# ETH10M100M_RMII_LAN8720.net
KiCad netlist of a schematic drawn in Altium Designer
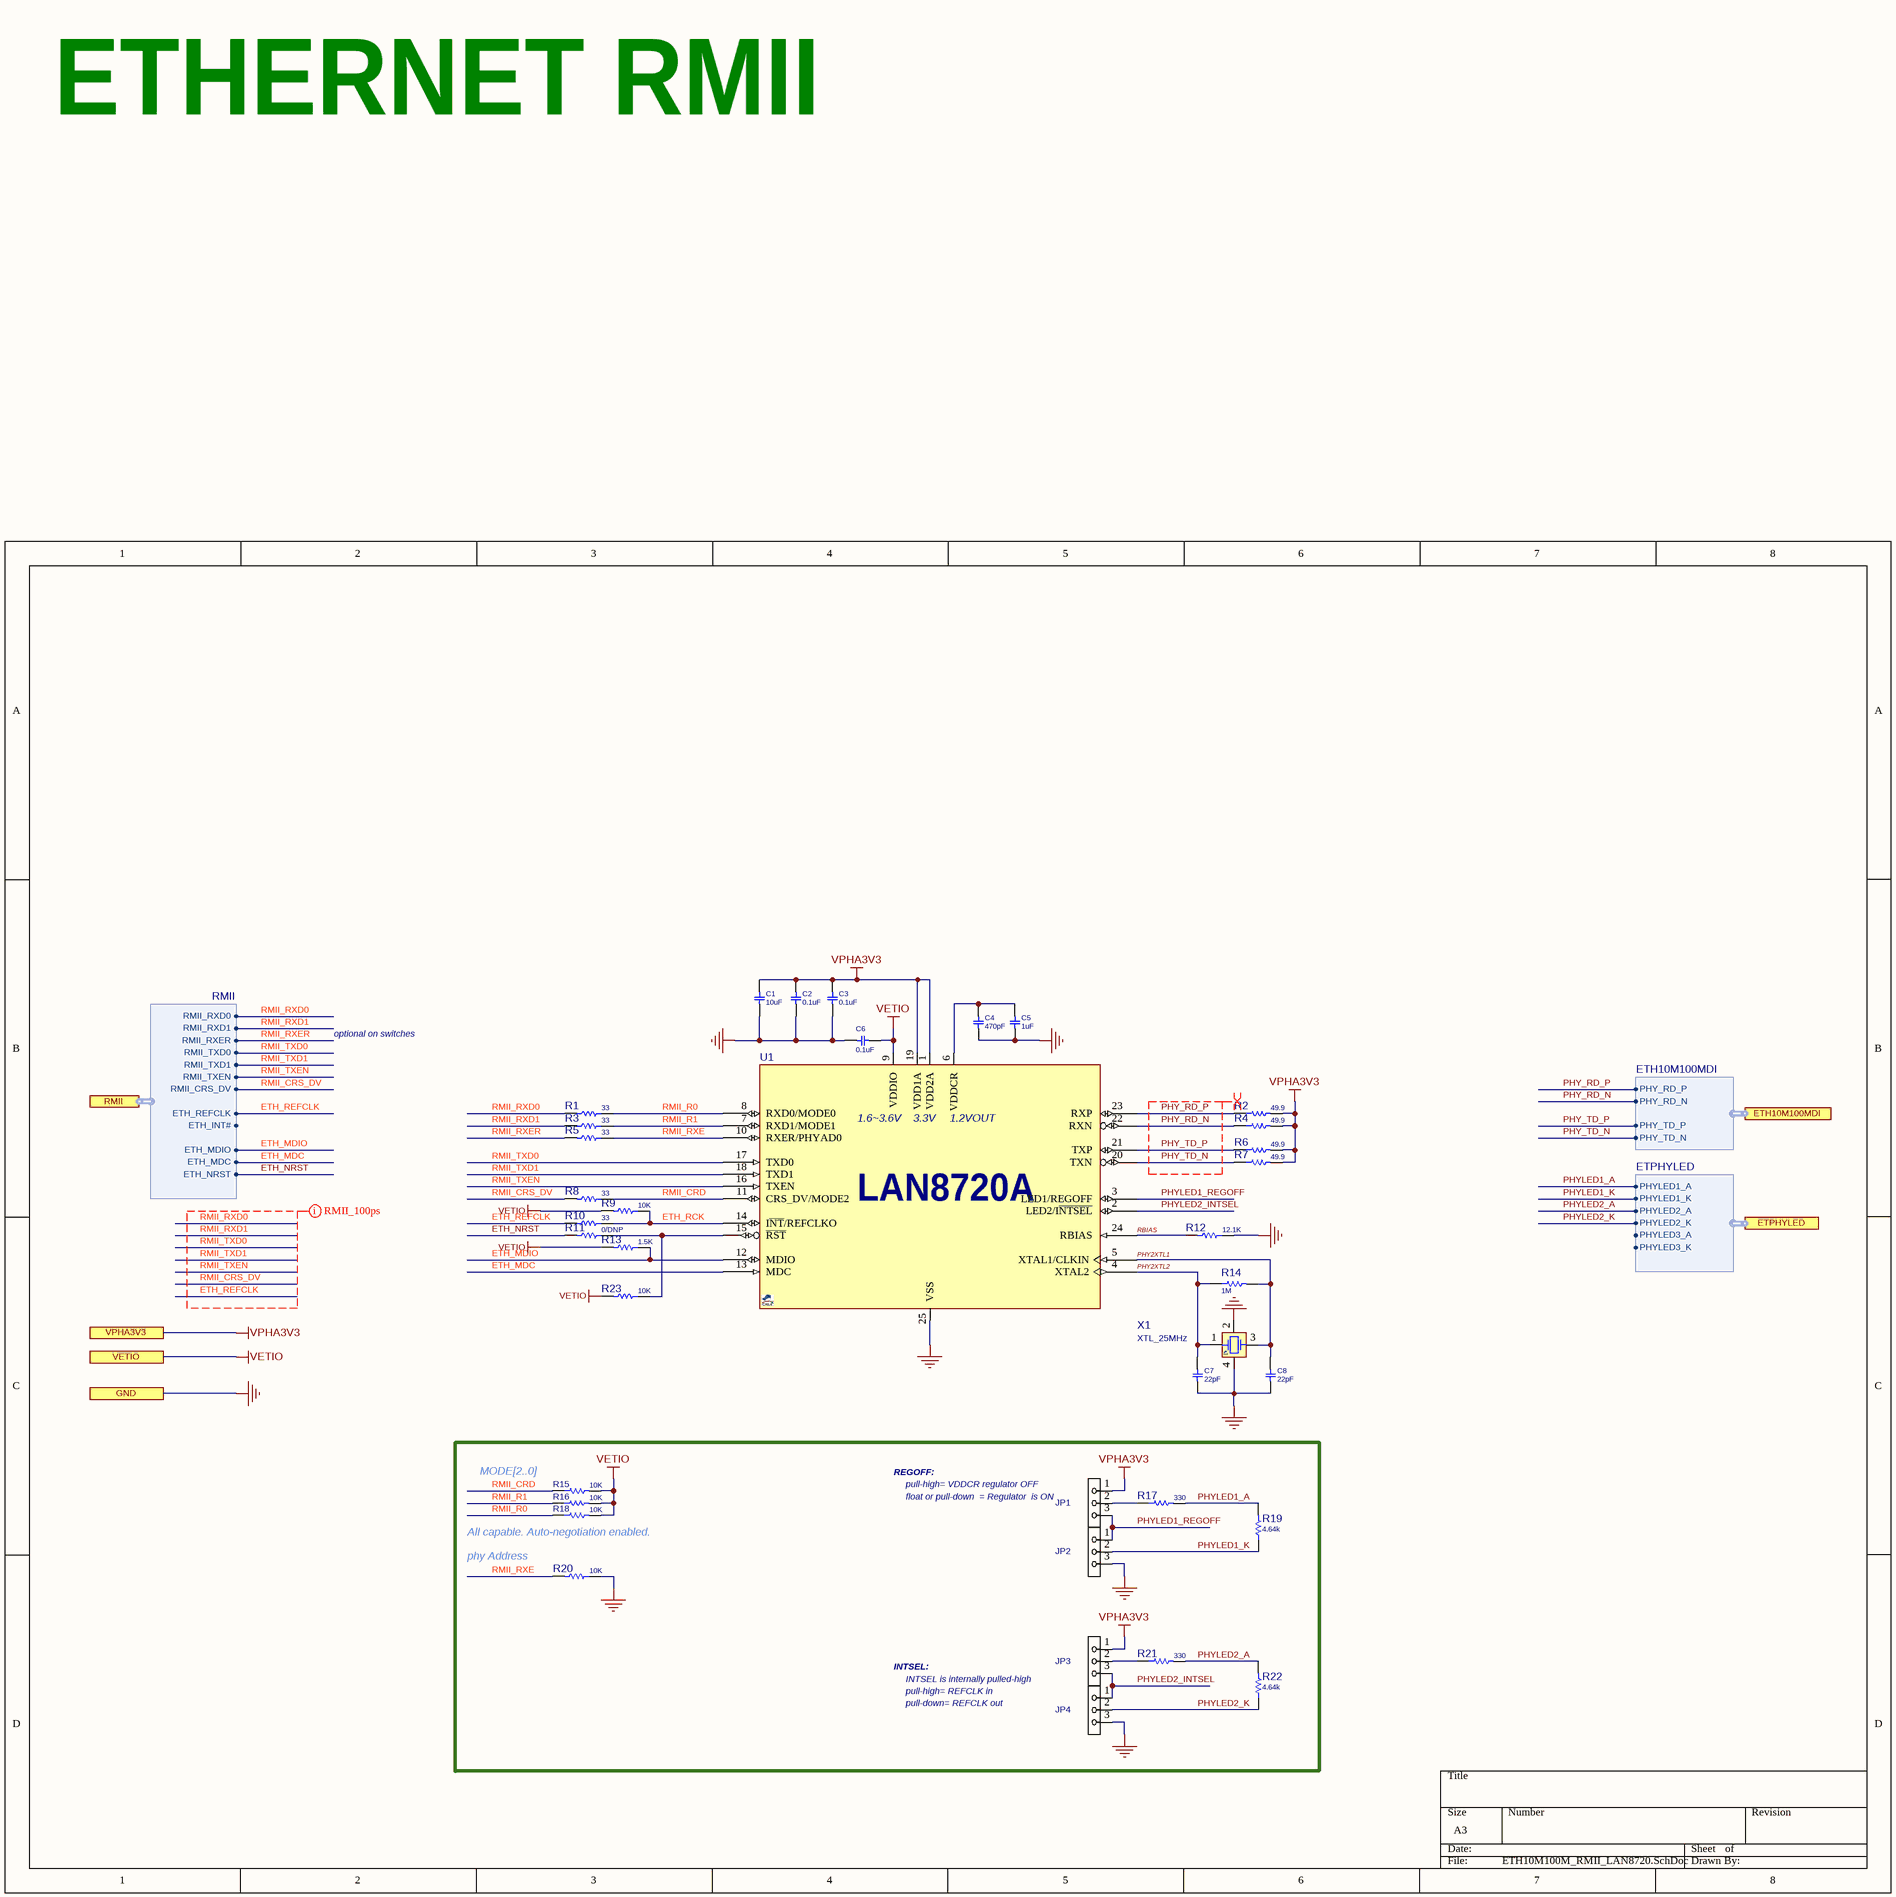
[diagram p0: ETH10M100M_RMII_LAN8720.SchDoc]

(export (version "E")
  (design (tool "Eeschema 10.0.6"))
  (components
    (comp (ref "C1")
      (value "10uF")
      (footprint "C0402")
      (description "CAP, MLCC")
      (libsource (lib "mlcc_smd_passive") (part "CAP_SMD_MLCC_100n50TDK"))
    )
    (comp (ref "C2")
      (value "0.1uF")
      (footprint "C0402")
      (description "CAP, MLCC")
      (libsource (lib "mlcc_smd_passive") (part "CAP_SMD_MLCC_100n50TDK"))
    )
    (comp (ref "C3")
      (value "0.1uF")
      (footprint "C0402")
      (description "CAP, MLCC")
      (libsource (lib "mlcc_smd_passive") (part "CAP_SMD_MLCC_100n50TDK"))
    )
    (comp (ref "C4")
      (value "470pF")
      (footprint "C0402")
      (description "CAP, MLCC")
      (libsource (lib "mlcc_smd_passive") (part "CAP_SMD_MLCC_100n50TDK"))
    )
    (comp (ref "C5")
      (value "1uF")
      (footprint "C0402")
      (description "CAP, MLCC")
      (libsource (lib "mlcc_smd_passive") (part "CAP_SMD_MLCC_100n50TDK"))
    )
    (comp (ref "C6")
      (value "0.1uF")
      (footprint "C0402")
      (description "CAP, MLCC")
      (libsource (lib "mlcc_smd_passive") (part "CAP_SMD_MLCC_100n50TDK"))
    )
    (comp (ref "C7")
      (value "22pF")
      (footprint "C0402")
      (description "CAP, MLCC")
      (libsource (lib "mlcc_smd_passive") (part "CAP_SMD_MLCC_100n50TDK"))
    )
    (comp (ref "C8")
      (value "22pF")
      (footprint "C0402")
      (description "CAP, MLCC")
      (libsource (lib "mlcc_smd_passive") (part "CAP_SMD_MLCC_100n50TDK"))
    )
    (comp (ref "JP1")
      (value "JMPHDR3PIN")
      (footprint "JP_3_60W")
      (description "JUMPER, HEADER 3PIN")
      (fields (field (name "MANF") "MANF") (field (name "MANF_P#") "MANF_P#"))
      (libsource (lib "test-tp_jumper") (part "JUMPER_SOLDER_3P"))
    )
    (comp (ref "JP2")
      (value "JMPHDR3PIN")
      (footprint "JP_3_60W")
      (description "JUMPER, HEADER 3PIN")
      (fields (field (name "MANF") "MANF") (field (name "MANF_P#") "MANF_P#"))
      (libsource (lib "test-tp_jumper") (part "JUMPER_SOLDER_3P"))
    )
    (comp (ref "JP3")
      (value "JMPHDR3PIN")
      (footprint "JP_3_60W")
      (description "JUMPER, HEADER 3PIN")
      (fields (field (name "MANF") "MANF") (field (name "MANF_P#") "MANF_P#"))
      (libsource (lib "test-tp_jumper") (part "JUMPER_SOLDER_3P"))
    )
    (comp (ref "JP4")
      (value "JMPHDR3PIN")
      (footprint "JP_3_60W")
      (description "JUMPER, HEADER 3PIN")
      (fields (field (name "MANF") "MANF") (field (name "MANF_P#") "MANF_P#"))
      (libsource (lib "test-tp_jumper") (part "JUMPER_SOLDER_3P"))
    )
    (comp (ref "R1")
      (value "33")
      (footprint "R0402")
      (description "RESISTOR, SMD, THICK FILM, YAGEO")
      (fields (field (name "MANF_P#") "RC0402FR-071KL") (field (name "MANF") "Yageo"))
      (libsource (lib "res_smd_Yageo0402_thickfilm") (part "RES_SMD_1K_0402YK"))
    )
    (comp (ref "R2")
      (value "49.9")
      (footprint "R0402")
      (description "RESISTOR, SMD, THICK FILM, YAGEO")
      (fields (field (name "MANF_P#") "RC0402FR-071KL") (field (name "MANF") "Yageo"))
      (libsource (lib "res_smd_Yageo0402_thickfilm") (part "RES_SMD_1K_0402YK"))
    )
    (comp (ref "R3")
      (value "33")
      (footprint "R0402")
      (description "RESISTOR, SMD, THICK FILM, YAGEO")
      (fields (field (name "MANF_P#") "RC0402FR-071KL") (field (name "MANF") "Yageo"))
      (libsource (lib "res_smd_Yageo0402_thickfilm") (part "RES_SMD_1K_0402YK"))
    )
    (comp (ref "R4")
      (value "49.9")
      (footprint "R0402")
      (description "RESISTOR, SMD, THICK FILM, YAGEO")
      (fields (field (name "MANF_P#") "RC0402FR-071KL") (field (name "MANF") "Yageo"))
      (libsource (lib "res_smd_Yageo0402_thickfilm") (part "RES_SMD_1K_0402YK"))
    )
    (comp (ref "R5")
      (value "33")
      (footprint "R0402")
      (description "RESISTOR, SMD, THICK FILM, YAGEO")
      (fields (field (name "MANF_P#") "RC0402FR-071KL") (field (name "MANF") "Yageo"))
      (libsource (lib "res_smd_Yageo0402_thickfilm") (part "RES_SMD_1K_0402YK"))
    )
    (comp (ref "R6")
      (value "49.9")
      (footprint "R0402")
      (description "RESISTOR, SMD, THICK FILM, YAGEO")
      (fields (field (name "MANF_P#") "RC0402FR-071KL") (field (name "MANF") "Yageo"))
      (libsource (lib "res_smd_Yageo0402_thickfilm") (part "RES_SMD_1K_0402YK"))
    )
    (comp (ref "R7")
      (value "49.9")
      (footprint "R0402")
      (description "RESISTOR, SMD, THICK FILM, YAGEO")
      (fields (field (name "MANF_P#") "RC0402FR-071KL") (field (name "MANF") "Yageo"))
      (libsource (lib "res_smd_Yageo0402_thickfilm") (part "RES_SMD_1K_0402YK"))
    )
    (comp (ref "R8")
      (value "33")
      (footprint "R0402")
      (description "RESISTOR, SMD, THICK FILM, YAGEO")
      (fields (field (name "MANF_P#") "RC0402FR-071KL") (field (name "MANF") "Yageo"))
      (libsource (lib "res_smd_Yageo0402_thickfilm") (part "RES_SMD_1K_0402YK"))
    )
    (comp (ref "R9")
      (value "10K")
      (footprint "R0402")
      (description "RESISTOR, SMD, THICK FILM, YAGEO")
      (fields (field (name "MANF_P#") "RC0402FR-071KL") (field (name "MANF") "Yageo"))
      (libsource (lib "res_smd_Yageo0402_thickfilm") (part "RES_SMD_1K_0402YK"))
    )
    (comp (ref "R10")
      (value "33")
      (footprint "R0402")
      (description "RESISTOR, SMD, THICK FILM, YAGEO")
      (fields (field (name "MANF_P#") "RC0402FR-071KL") (field (name "MANF") "Yageo"))
      (libsource (lib "res_smd_Yageo0402_thickfilm") (part "RES_SMD_1K_0402YK"))
    )
    (comp (ref "R11")
      (value "0/DNP")
      (footprint "R0402")
      (description "RESISTOR, SMD, THICK FILM, YAGEO")
      (fields (field (name "MANF_P#") "RC0402FR-071KL") (field (name "MANF") "Yageo"))
      (libsource (lib "res_smd_Yageo0402_thickfilm") (part "RES_SMD_1K_0402YK"))
    )
    (comp (ref "R12")
      (value "12.1K")
      (footprint "R0402")
      (description "RESISTOR, SMD, THICK FILM, YAGEO")
      (fields (field (name "MANF_P#") "RC0402FR-071KL") (field (name "MANF") "Yageo"))
      (libsource (lib "res_smd_Yageo0402_thickfilm") (part "RES_SMD_1K_0402YK"))
    )
    (comp (ref "R13")
      (value "1.5K")
      (footprint "R0402")
      (description "RESISTOR, SMD, THICK FILM, YAGEO")
      (fields (field (name "MANF_P#") "RC0402FR-071KL") (field (name "MANF") "Yageo"))
      (libsource (lib "res_smd_Yageo0402_thickfilm") (part "RES_SMD_1K_0402YK"))
    )
    (comp (ref "R14")
      (value "1M")
      (footprint "R0402")
      (description "RESISTOR, SMD")
      (fields (field (name "MANF") "Yageo") (field (name "MANF_P#") "RC0402FR-071ML"))
      (libsource (lib "res_smd_KoaSpeer0402") (part "RES_SMD_10K_0402"))
    )
    (comp (ref "R15")
      (value "10K")
      (footprint "R0402")
      (description "RESISTOR, SMD, THICK FILM, YAGEO")
      (fields (field (name "MANF_P#") "RC0402FR-071KL") (field (name "MANF") "Yageo"))
      (libsource (lib "res_smd_Yageo0402_thickfilm") (part "RES_SMD_1K_0402YK"))
    )
    (comp (ref "R16")
      (value "10K")
      (footprint "R0402")
      (description "RESISTOR, SMD, THICK FILM, YAGEO")
      (fields (field (name "MANF_P#") "RC0402FR-071KL") (field (name "MANF") "Yageo"))
      (libsource (lib "res_smd_Yageo0402_thickfilm") (part "RES_SMD_1K_0402YK"))
    )
    (comp (ref "R17")
      (value "330")
      (footprint "R0402")
      (description "RESISTOR, SMD, THICK FILM, YAGEO")
      (fields (field (name "MANF_P#") "RC0402FR-071KL") (field (name "MANF") "Yageo"))
      (libsource (lib "res_smd_Yageo0402_thickfilm") (part "RES_SMD_1K_0402YK"))
    )
    (comp (ref "R18")
      (value "10K")
      (footprint "R0402")
      (description "RESISTOR, SMD, THICK FILM, YAGEO")
      (fields (field (name "MANF_P#") "RC0402FR-071KL") (field (name "MANF") "Yageo"))
      (libsource (lib "res_smd_Yageo0402_thickfilm") (part "RES_SMD_1K_0402YK"))
    )
    (comp (ref "R19")
      (value "4.64k")
      (footprint "R0402")
      (description "RESISTOR, SMD, THICK FILM, YAGEO")
      (fields (field (name "MANF_P#") "RC0402FR-071KL") (field (name "MANF") "Yageo"))
      (libsource (lib "res_smd_Yageo0402_thickfilm") (part "RES_SMD_1K_0402YK"))
    )
    (comp (ref "R20")
      (value "10K")
      (footprint "R0402")
      (description "RESISTOR, SMD, THICK FILM, YAGEO")
      (fields (field (name "MANF_P#") "RC0402FR-071KL") (field (name "MANF") "Yageo"))
      (libsource (lib "res_smd_Yageo0402_thickfilm") (part "RES_SMD_1K_0402YK"))
    )
    (comp (ref "R21")
      (value "330")
      (footprint "R0402")
      (description "RESISTOR, SMD, THICK FILM, YAGEO")
      (fields (field (name "MANF_P#") "RC0402FR-071KL") (field (name "MANF") "Yageo"))
      (libsource (lib "res_smd_Yageo0402_thickfilm") (part "RES_SMD_1K_0402YK"))
    )
    (comp (ref "R22")
      (value "4.64k")
      (footprint "R0402")
      (description "RESISTOR, SMD, THICK FILM, YAGEO")
      (fields (field (name "MANF_P#") "RC0402FR-071KL") (field (name "MANF") "Yageo"))
      (libsource (lib "res_smd_Yageo0402_thickfilm") (part "RES_SMD_1K_0402YK"))
    )
    (comp (ref "R23")
      (value "10K")
      (footprint "R0402")
      (description "RESISTOR, SMD, THICK FILM, YAGEO")
      (fields (field (name "MANF_P#") "RC0402FR-071KL") (field (name "MANF") "Yageo"))
      (libsource (lib "res_smd_Yageo0402_thickfilm") (part "RES_SMD_1K_0402YK"))
    )
    (comp (ref "U1")
      (value "LAN8720A")
      (footprint "QFN50_24T")
      (description "Ethernet Transceiver, 10/100, RMII, 1.6-3.6V QFN24")
      (fields (field (name "MANF") "SMSC") (field (name "MANF_P#") "LAN8720A-CP-TR"))
      (libsource (lib "ethernet") (part "LAN8720A_QFN24"))
    )
    (comp (ref "X1")
      (value "XTL_25MHz")
      (footprint "XTL_4_3225")
      (description "CRYSTAL 25.00 MHZ 18pF, 10PPM")
      (fields (field (name "MANF") "EPSON") (field (name "MANF_P#") "TSX-3225 25.0000MF10P-C3"))
      (libsource (lib "crystal_osc") (part "XTL_4_25MHz_3225"))
    )
  )
  (nets
    (net (code "4") (name "/ETH_MDC") (class "Default")
      (node (ref "U1") (pin "13") (pinfunction "MDC_13") (pintype "input"))
    )
    (net (code "5") (name "/ETH_MDIO") (class "Default")
      (node (ref "R13") (pin "1") (pinfunction "1_1") (pintype "passive"))
      (node (ref "U1") (pin "12") (pinfunction "MDIO_12") (pintype "bidirectional"))
    )
    (net (code "6") (name "/ETH_NRST") (class "Default")
      (node (ref "R11") (pin "2") (pinfunction "2_2") (pintype "passive"))
    )
    (net (code "7") (name "/ETH_RCK") (class "Default")
      (node (ref "R10") (pin "1") (pinfunction "1_1") (pintype "passive"))
      (node (ref "R9") (pin "1") (pinfunction "1_1") (pintype "passive"))
      (node (ref "U1") (pin "14") (pinfunction "I~{NT}/REFCLKO_14") (pintype "bidirectional"))
    )
    (net (code "8") (name "/ETH_REFCLK") (class "Default")
      (node (ref "R10") (pin "2") (pinfunction "2_2") (pintype "passive"))
    )
    (net (code "9") (name "/PHY2XTL1") (class "Default")
      (node (ref "C8") (pin "1") (pinfunction "1_1") (pintype "passive"))
      (node (ref "R14") (pin "2") (pinfunction "2_2") (pintype "passive"))
      (node (ref "U1") (pin "5") (pinfunction "XTAL1/CLKIN_5") (pintype "input"))
      (node (ref "X1") (pin "3") (pinfunction "XB_3") (pintype "passive"))
    )
    (net (code "10") (name "/PHY2XTL2") (class "Default")
      (node (ref "C7") (pin "1") (pinfunction "1_1") (pintype "passive"))
      (node (ref "R14") (pin "1") (pinfunction "1_1") (pintype "passive"))
      (node (ref "U1") (pin "4") (pinfunction "XTAL2_4") (pintype "output"))
      (node (ref "X1") (pin "1") (pinfunction "XA_1") (pintype "passive"))
    )
    (net (code "11") (name "/PHYLED1_A") (class "Default")
      (node (ref "R17") (pin "2") (pinfunction "2_2") (pintype "passive"))
      (node (ref "R19") (pin "2") (pinfunction "2_2") (pintype "passive"))
    )
    (net (code "12") (name "/PHYLED1_K") (class "Default")
      (node (ref "JP2") (pin "2") (pinfunction "2_2") (pintype "passive"))
      (node (ref "R19") (pin "1") (pinfunction "1_1") (pintype "passive"))
    )
    (net (code "13") (name "/PHYLED1_REGOFF") (class "Default")
      (node (ref "JP1") (pin "3") (pinfunction "3_3") (pintype "passive"))
      (node (ref "JP2") (pin "1") (pinfunction "1_1") (pintype "passive"))
      (node (ref "U1") (pin "3") (pinfunction "LED1/REGOFF_3") (pintype "bidirectional"))
    )
    (net (code "14") (name "/PHYLED2_A") (class "Default")
      (node (ref "R21") (pin "2") (pinfunction "2_2") (pintype "passive"))
      (node (ref "R22") (pin "2") (pinfunction "2_2") (pintype "passive"))
    )
    (net (code "15") (name "/PHYLED2_INTSEL") (class "Default")
      (node (ref "JP3") (pin "3") (pinfunction "3_3") (pintype "passive"))
      (node (ref "JP4") (pin "1") (pinfunction "1_1") (pintype "passive"))
      (node (ref "U1") (pin "2") (pinfunction "LED2/I~{NTSEL}_2") (pintype "bidirectional"))
    )
    (net (code "16") (name "/PHYLED2_K") (class "Default")
      (node (ref "JP4") (pin "2") (pinfunction "2_2") (pintype "passive"))
      (node (ref "R22") (pin "1") (pinfunction "1_1") (pintype "passive"))
    )
    (net (code "17") (name "/PHY_RD_N") (class "Default")
      (node (ref "R4") (pin "1") (pinfunction "1_1") (pintype "passive"))
      (node (ref "U1") (pin "22") (pinfunction "RXN_22") (pintype "bidirectional"))
    )
    (net (code "18") (name "/PHY_RD_P") (class "Default")
      (node (ref "R2") (pin "1") (pinfunction "1_1") (pintype "passive"))
      (node (ref "U1") (pin "23") (pinfunction "RXP_23") (pintype "bidirectional"))
    )
    (net (code "19") (name "/PHY_TD_N") (class "Default")
      (node (ref "R7") (pin "1") (pinfunction "1_1") (pintype "passive"))
      (node (ref "U1") (pin "20") (pinfunction "TXN_20") (pintype "bidirectional"))
    )
    (net (code "20") (name "/PHY_TD_P") (class "Default")
      (node (ref "R6") (pin "1") (pinfunction "1_1") (pintype "passive"))
      (node (ref "U1") (pin "21") (pinfunction "TXP_21") (pintype "bidirectional"))
    )
    (net (code "21") (name "/RBIAS") (class "Default")
      (node (ref "R12") (pin "2") (pinfunction "2_2") (pintype "passive"))
      (node (ref "U1") (pin "24") (pinfunction "RBIAS_24") (pintype "input"))
    )
    (net (code "22") (name "/RMII_CRD") (class "Default")
      (node (ref "R15") (pin "1") (pinfunction "1_1") (pintype "passive"))
      (node (ref "R8") (pin "1") (pinfunction "1_1") (pintype "passive"))
      (node (ref "U1") (pin "11") (pinfunction "CRS_DV/MODE2_11") (pintype "bidirectional"))
    )
    (net (code "23") (name "/RMII_CRS_DV") (class "Default")
      (node (ref "R8") (pin "2") (pinfunction "2_2") (pintype "passive"))
    )
    (net (code "24") (name "/RMII_R0") (class "Default")
      (node (ref "R1") (pin "1") (pinfunction "1_1") (pintype "passive"))
      (node (ref "R18") (pin "1") (pinfunction "1_1") (pintype "passive"))
      (node (ref "U1") (pin "8") (pinfunction "RXD0/MODE0_8") (pintype "bidirectional"))
    )
    (net (code "25") (name "/RMII_R1") (class "Default")
      (node (ref "R16") (pin "1") (pinfunction "1_1") (pintype "passive"))
      (node (ref "R3") (pin "1") (pinfunction "1_1") (pintype "passive"))
      (node (ref "U1") (pin "7") (pinfunction "RXD1/MODE1_7") (pintype "bidirectional"))
    )
    (net (code "26") (name "/RMII_RXD0") (class "Default")
      (node (ref "R1") (pin "2") (pinfunction "2_2") (pintype "passive"))
    )
    (net (code "27") (name "/RMII_RXD1") (class "Default")
      (node (ref "R3") (pin "2") (pinfunction "2_2") (pintype "passive"))
    )
    (net (code "28") (name "/RMII_RXE") (class "Default")
      (node (ref "R20") (pin "2") (pinfunction "2_2") (pintype "passive"))
      (node (ref "R5") (pin "1") (pinfunction "1_1") (pintype "passive"))
      (node (ref "U1") (pin "10") (pinfunction "RXER/PHYAD0_10") (pintype "bidirectional"))
    )
    (net (code "29") (name "/RMII_RXER") (class "Default")
      (node (ref "R5") (pin "2") (pinfunction "2_2") (pintype "passive"))
    )
    (net (code "30") (name "/RMII_TXD0") (class "Default")
      (node (ref "U1") (pin "17") (pinfunction "TXD0_17") (pintype "input"))
    )
    (net (code "31") (name "/RMII_TXD1") (class "Default")
      (node (ref "U1") (pin "18") (pinfunction "TXD1_18") (pintype "input"))
    )
    (net (code "32") (name "/RMII_TXEN") (class "Default")
      (node (ref "U1") (pin "16") (pinfunction "TXEN_16") (pintype "input"))
    )
    (net (code "36") (name "GND") (class "Default")
      (node (ref "C1") (pin "2") (pinfunction "2_2") (pintype "passive"))
      (node (ref "C2") (pin "2") (pinfunction "2_2") (pintype "passive"))
      (node (ref "C3") (pin "2") (pinfunction "2_2") (pintype "passive"))
      (node (ref "C4") (pin "2") (pinfunction "2_2") (pintype "passive"))
      (node (ref "C5") (pin "2") (pinfunction "2_2") (pintype "passive"))
      (node (ref "C6") (pin "2") (pinfunction "2_2") (pintype "passive"))
      (node (ref "C7") (pin "2") (pinfunction "2_2") (pintype "passive"))
      (node (ref "C8") (pin "2") (pinfunction "2_2") (pintype "passive"))
      (node (ref "JP2") (pin "3") (pinfunction "3_3") (pintype "passive"))
      (node (ref "JP4") (pin "3") (pinfunction "3_3") (pintype "passive"))
      (node (ref "R12") (pin "1") (pinfunction "1_1") (pintype "passive"))
      (node (ref "R20") (pin "1") (pinfunction "1_1") (pintype "passive"))
      (node (ref "U1") (pin "25") (pinfunction "VSS_25") (pintype "power_in"))
      (node (ref "X1") (pin "2") (pinfunction "GND1_2") (pintype "passive"))
      (node (ref "X1") (pin "4") (pinfunction "GND2_4") (pintype "passive"))
    )
    (net (code "37") (name "Net-(JP1-Pad2)") (class "Default")
      (node (ref "JP1") (pin "2") (pinfunction "2_2") (pintype "passive"))
      (node (ref "R17") (pin "1") (pinfunction "1_1") (pintype "passive"))
    )
    (net (code "38") (name "Net-(JP3-Pad2)") (class "Default")
      (node (ref "JP3") (pin "2") (pinfunction "2_2") (pintype "passive"))
      (node (ref "R21") (pin "1") (pinfunction "1_1") (pintype "passive"))
    )
    (net (code "39") (name "Net-(U1-VDDCR)") (class "Default")
      (node (ref "C4") (pin "1") (pinfunction "1_1") (pintype "passive"))
      (node (ref "C5") (pin "1") (pinfunction "1_1") (pintype "passive"))
      (node (ref "U1") (pin "6") (pinfunction "VDDCR_6") (pintype "power_in"))
    )
    (net (code "40") (name "Net-(U1-~{RST})") (class "Default")
      (node (ref "R11") (pin "1") (pinfunction "1_1") (pintype "passive"))
      (node (ref "R23") (pin "1") (pinfunction "1_1") (pintype "passive"))
      (node (ref "U1") (pin "15") (pinfunction "~{RST}_15") (pintype "bidirectional"))
    )
    (net (code "41") (name "VETIO") (class "Default")
      (node (ref "C6") (pin "1") (pinfunction "1_1") (pintype "passive"))
      (node (ref "R13") (pin "2") (pinfunction "2_2") (pintype "passive"))
      (node (ref "R15") (pin "2") (pinfunction "2_2") (pintype "passive"))
      (node (ref "R16") (pin "2") (pinfunction "2_2") (pintype "passive"))
      (node (ref "R18") (pin "2") (pinfunction "2_2") (pintype "passive"))
      (node (ref "R23") (pin "2") (pinfunction "2_2") (pintype "passive"))
      (node (ref "R9") (pin "2") (pinfunction "2_2") (pintype "passive"))
      (node (ref "U1") (pin "9") (pinfunction "VDDIO_9") (pintype "power_in"))
    )
    (net (code "42") (name "VPHA3V3") (class "Default")
      (node (ref "C1") (pin "1") (pinfunction "1_1") (pintype "passive"))
      (node (ref "C2") (pin "1") (pinfunction "1_1") (pintype "passive"))
      (node (ref "C3") (pin "1") (pinfunction "1_1") (pintype "passive"))
      (node (ref "JP1") (pin "1") (pinfunction "1_1") (pintype "passive"))
      (node (ref "JP3") (pin "1") (pinfunction "1_1") (pintype "passive"))
      (node (ref "R2") (pin "2") (pinfunction "2_2") (pintype "passive"))
      (node (ref "R4") (pin "2") (pinfunction "2_2") (pintype "passive"))
      (node (ref "R6") (pin "2") (pinfunction "2_2") (pintype "passive"))
      (node (ref "R7") (pin "2") (pinfunction "2_2") (pintype "passive"))
      (node (ref "U1") (pin "1") (pinfunction "VDD2A_1") (pintype "power_in"))
      (node (ref "U1") (pin "19") (pinfunction "VDD1A_19") (pintype "power_in"))
    )
  )
)
